# 07_EL_CON.net
KiCad netlist of a schematic drawn in Altium Designer
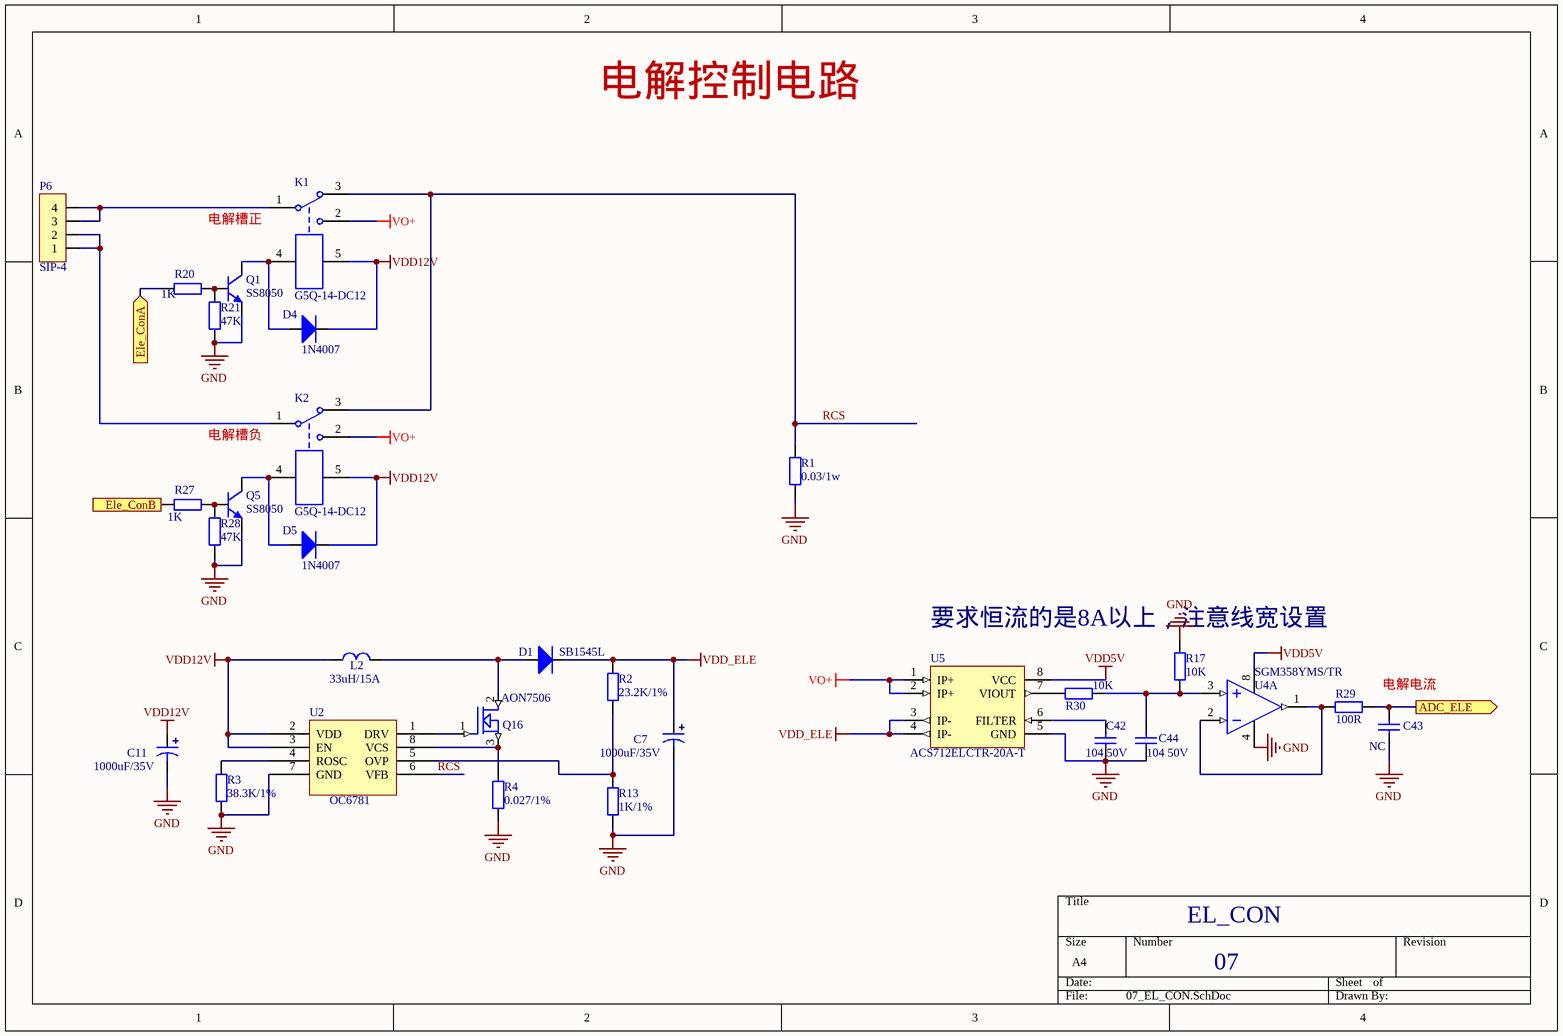
[diagram p0: 07_EL_CON.SchDoc]

(export (version "E")
  (design (tool "Eeschema 10.0.6"))
  (components
    (comp (ref "C7")
      (value "1000uF/35V")
      (footprint "10*16")
      (description "电解电容")
      (libsource (lib "XiaoyI") (part "CAP2"))
    )
    (comp (ref "C11")
      (value "1000uF/35V")
      (footprint "10*16")
      (description "电解电容")
      (libsource (lib "XiaoyI") (part "CAP2"))
    )
    (comp (ref "C42")
      (value "104 50V")
      (footprint "SMD-0603C")
      (description "贴片电容 10%")
      (libsource (lib "XiaoyI") (part "CAP4"))
    )
    (comp (ref "C43")
      (value "NC")
      (footprint "SMD-0603C")
      (description "贴片电容 10%")
      (libsource (lib "XiaoyI") (part "CAP4"))
    )
    (comp (ref "C44")
      (value "104 50V")
      (footprint "SMD-0603C")
      (description "贴片电容 10%")
      (libsource (lib "XiaoyI") (part "CAP4"))
    )
    (comp (ref "D1")
      (value "SB1545L")
      (footprint "TO227")
      (description "肖特基二极管")
      (libsource (lib "XiaoyI") (part "DIODE2"))
    )
    (comp (ref "D4")
      (value "1N4007")
      (footprint "DO-214-AC")
      (description "贴片二极管")
      (libsource (lib "XiaoyI") (part "DIODE2"))
    )
    (comp (ref "D5")
      (value "1N4007")
      (footprint "DO-214-AC")
      (description "贴片二极管")
      (libsource (lib "XiaoyI") (part "DIODE2"))
    )
    (comp (ref "K1")
      (value "G5Q-14-DC12")
      (footprint "G5Q-14")
      (description "5V 继电器")
      (libsource (lib "XiaoyI") (part "JDQ1"))
    )
    (comp (ref "K2")
      (value "G5Q-14-DC12")
      (footprint "G5Q-14")
      (description "5V 继电器")
      (libsource (lib "XiaoyI") (part "JDQ1"))
    )
    (comp (ref "L2")
      (value "33uH/15A")
      (footprint "INDUCTOR_34*18")
      (description "10uH 1A")
      (libsource (lib "XiaoyI") (part "Inductor1"))
    )
    (comp (ref "P6")
      (value "SIP-4")
      (footprint "VH-AW-3.96*4P")
      (description "3.96 4P 直插")
      (libsource (lib "XiaoyI") (part "SIP-4"))
    )
    (comp (ref "Q1")
      (value "SS8050")
      (footprint "SOT-23")
      (description "三极管")
      (libsource (lib "XiaoyI") (part "NPN-1"))
    )
    (comp (ref "Q5")
      (value "SS8050")
      (footprint "SOT-23")
      (description "三极管")
      (libsource (lib "XiaoyI") (part "NPN-1"))
    )
    (comp (ref "Q16")
      (value "AON7506")
      (footprint "DFN3*3-8")
      (description "MOSFET N")
      (libsource (lib "XiaoyI") (part "MOSFET N"))
    )
    (comp (ref "R1")
      (value "0.03/1w")
      (footprint "2512R")
      (description "贴片电阻 5%")
      (libsource (lib "") (part "RES2_1"))
    )
    (comp (ref "R2")
      (value "23.2K/1%")
      (footprint "SMD-0603")
      (description "贴片电阻 5%")
      (libsource (lib "") (part "RES2_1"))
    )
    (comp (ref "R3")
      (value "38.3K/1%")
      (footprint "SMD-0603")
      (description "贴片电阻 5%")
      (libsource (lib "") (part "RES2_1"))
    )
    (comp (ref "R4")
      (value "0.027/1%")
      (footprint "2512r")
      (description "贴片电阻 5%")
      (libsource (lib "") (part "RES2_1"))
    )
    (comp (ref "R13")
      (value "1K/1%")
      (footprint "SMD-0603")
      (description "贴片电阻 5%")
      (libsource (lib "") (part "RES2_1"))
    )
    (comp (ref "R17")
      (value "10K")
      (footprint "SMD-0603")
      (description "贴片电阻 1%")
      (libsource (lib "") (part "RES0_1"))
    )
    (comp (ref "R20")
      (value "1K")
      (footprint "SMD-0603")
      (description "贴片电阻 5%")
      (libsource (lib "XiaoyI") (part "RES2"))
    )
    (comp (ref "R21")
      (value "47K")
      (footprint "SMD-0603")
      (description "贴片电阻 5%")
      (libsource (lib "") (part "RES2_2"))
    )
    (comp (ref "R27")
      (value "1K")
      (footprint "SMD-0603")
      (description "贴片电阻 5%")
      (libsource (lib "XiaoyI") (part "RES2"))
    )
    (comp (ref "R28")
      (value "47K")
      (footprint "SMD-0603")
      (description "贴片电阻 5%")
      (libsource (lib "") (part "RES2_2"))
    )
    (comp (ref "R29")
      (value "100R")
      (footprint "SMD-0603")
      (description "贴片电阻 5%")
      (libsource (lib "ABB") (part "RES0"))
    )
    (comp (ref "R30")
      (value "10K")
      (footprint "SMD-0603")
      (description "贴片电阻 1%")
      (libsource (lib "ABB") (part "RES0"))
    )
    (comp (ref "U2")
      (value "OC6781")
      (footprint "SOP127P600X265_HS-9N")
      (libsource (lib "stm32") (part "OC6781"))
    )
    (comp (ref "U4")
      (value "SGM358YMS/TR")
      (footprint "MSOP-8")
      (description "运算放大器")
      (libsource (lib "XiaoyI") (part "LM358"))
    )
    (comp (ref "U5")
      (value "ACS712ELCTR-20A-T")
      (footprint "SO-8")
      (description "HALL 20A 电流传感器")
      (libsource (lib "XiaoyI") (part "ACS712"))
    )
  )
  (nets
    (net (code "1") (name "/ADC_ELE") (class "Default")
      (node (ref "C43") (pin "2") (pinfunction "2_2") (pintype "passive"))
      (node (ref "R29") (pin "1") (pinfunction "1_1") (pintype "passive"))
    )
    (net (code "2") (name "/Ele_ConA") (class "Default")
      (node (ref "R20") (pin "1") (pinfunction "1_1") (pintype "passive"))
    )
    (net (code "3") (name "/Ele_ConB") (class "Default")
      (node (ref "R27") (pin "1") (pinfunction "1_1") (pintype "passive"))
    )
    (net (code "4") (name "/RCS") (class "Default")
      (node (ref "K1") (pin "3") (pinfunction "3_3") (pintype "passive"))
      (node (ref "K2") (pin "3") (pinfunction "3_3") (pintype "passive"))
      (node (ref "R1") (pin "1") (pinfunction "1_1") (pintype "passive"))
      (node (ref "U2") (pin "6") (pinfunction "VFB_6") (pintype "passive"))
    )
    (net (code "5") (name "GND") (class "Default")
      (node (ref "C11") (pin "2") (pinfunction "2_2") (pintype "passive"))
      (node (ref "C42") (pin "2") (pinfunction "2_2") (pintype "passive"))
      (node (ref "C43") (pin "1") (pinfunction "1_1") (pintype "passive"))
      (node (ref "C44") (pin "2") (pinfunction "2_2") (pintype "passive"))
      (node (ref "C7") (pin "2") (pinfunction "2_2") (pintype "passive"))
      (node (ref "Q1") (pin "2") (pinfunction "E_2") (pintype "passive"))
      (node (ref "Q5") (pin "2") (pinfunction "E_2") (pintype "passive"))
      (node (ref "R1") (pin "2") (pinfunction "2_2") (pintype "passive"))
      (node (ref "R13") (pin "2") (pinfunction "2_2") (pintype "passive"))
      (node (ref "R17") (pin "1") (pinfunction "1_1") (pintype "passive"))
      (node (ref "R21") (pin "1") (pinfunction "1_1") (pintype "passive"))
      (node (ref "R28") (pin "1") (pinfunction "1_1") (pintype "passive"))
      (node (ref "R3") (pin "2") (pinfunction "2_2") (pintype "passive"))
      (node (ref "R4") (pin "2") (pinfunction "2_2") (pintype "passive"))
      (node (ref "U2") (pin "7") (pinfunction "GND_7") (pintype "passive"))
      (node (ref "U4") (pin "4") (pinfunction "V-_4") (pintype "power_in"))
      (node (ref "U5") (pin "5") (pinfunction "GND_5") (pintype "power_in"))
    )
    (net (code "6") (name "Net-(D1-A)") (class "Default")
      (node (ref "D1") (pin "1") (pinfunction "A_1") (pintype "passive"))
      (node (ref "L2") (pin "2") (pinfunction "2_2") (pintype "passive"))
      (node (ref "Q16") (pin "2") (pinfunction "D_2") (pintype "input"))
    )
    (net (code "7") (name "Net-(D4-A)") (class "Default")
      (node (ref "D4") (pin "1") (pinfunction "A_1") (pintype "passive"))
      (node (ref "K1") (pin "4") (pinfunction "4_4") (pintype "passive"))
      (node (ref "Q1") (pin "3") (pinfunction "C_3") (pintype "passive"))
    )
    (net (code "8") (name "Net-(D5-A)") (class "Default")
      (node (ref "D5") (pin "1") (pinfunction "A_1") (pintype "passive"))
      (node (ref "K2") (pin "4") (pinfunction "4_4") (pintype "passive"))
      (node (ref "Q5") (pin "3") (pinfunction "C_3") (pintype "passive"))
    )
    (net (code "9") (name "Net-(K1-Pad1)") (class "Default")
      (node (ref "K1") (pin "1") (pinfunction "1_1") (pintype "passive"))
      (node (ref "P6") (pin "3") (pinfunction "3_3") (pintype "passive"))
      (node (ref "P6") (pin "4") (pinfunction "4_4") (pintype "passive"))
    )
    (net (code "10") (name "Net-(K2-Pad1)") (class "Default")
      (node (ref "K2") (pin "1") (pinfunction "1_1") (pintype "passive"))
      (node (ref "P6") (pin "1") (pinfunction "1_1") (pintype "passive"))
      (node (ref "P6") (pin "2") (pinfunction "2_2") (pintype "passive"))
    )
    (net (code "11") (name "Net-(Q1-B)") (class "Default")
      (node (ref "Q1") (pin "1") (pinfunction "B_1") (pintype "passive"))
      (node (ref "R20") (pin "2") (pinfunction "2_2") (pintype "passive"))
      (node (ref "R21") (pin "2") (pinfunction "2_2") (pintype "passive"))
    )
    (net (code "12") (name "Net-(Q5-B)") (class "Default")
      (node (ref "Q5") (pin "1") (pinfunction "B_1") (pintype "passive"))
      (node (ref "R27") (pin "2") (pinfunction "2_2") (pintype "passive"))
      (node (ref "R28") (pin "2") (pinfunction "2_2") (pintype "passive"))
    )
    (net (code "13") (name "Net-(Q16-G)") (class "Default")
      (node (ref "Q16") (pin "1") (pinfunction "G_1") (pintype "input"))
      (node (ref "U2") (pin "1") (pinfunction "DRV_1") (pintype "passive"))
    )
    (net (code "14") (name "Net-(Q16-S)") (class "Default")
      (node (ref "Q16") (pin "3") (pinfunction "S_3") (pintype "output"))
      (node (ref "R4") (pin "1") (pinfunction "1_1") (pintype "passive"))
      (node (ref "U2") (pin "8") (pinfunction "VCS_8") (pintype "passive"))
    )
    (net (code "15") (name "Net-(U2-OVP)") (class "Default")
      (node (ref "R13") (pin "1") (pinfunction "1_1") (pintype "passive"))
      (node (ref "R2") (pin "2") (pinfunction "2_2") (pintype "passive"))
      (node (ref "U2") (pin "5") (pinfunction "OVP_5") (pintype "passive"))
    )
    (net (code "16") (name "Net-(U2-ROSC)") (class "Default")
      (node (ref "R3") (pin "1") (pinfunction "1_1") (pintype "passive"))
      (node (ref "U2") (pin "4") (pinfunction "ROSC_4") (pintype "passive"))
    )
    (net (code "17") (name "Net-(U4A-IN1+)") (class "Default")
      (node (ref "C44") (pin "1") (pinfunction "1_1") (pintype "passive"))
      (node (ref "R17") (pin "2") (pinfunction "2_2") (pintype "passive"))
      (node (ref "R30") (pin "1") (pinfunction "1_1") (pintype "passive"))
      (node (ref "U4") (pin "3") (pinfunction "IN1+_3") (pintype "input"))
    )
    (net (code "18") (name "Net-(U4A-IN1-)") (class "Default")
      (node (ref "R29") (pin "2") (pinfunction "2_2") (pintype "passive"))
      (node (ref "U4") (pin "1") (pinfunction "OUT1_1") (pintype "output"))
      (node (ref "U4") (pin "2") (pinfunction "IN1-_2") (pintype "input"))
    )
    (net (code "19") (name "Net-(U5-FILTER)") (class "Default")
      (node (ref "C42") (pin "1") (pinfunction "1_1") (pintype "passive"))
      (node (ref "U5") (pin "6") (pinfunction "FILTER_6") (pintype "input"))
    )
    (net (code "20") (name "Net-(U5-VIOUT)") (class "Default")
      (node (ref "R30") (pin "2") (pinfunction "2_2") (pintype "passive"))
      (node (ref "U5") (pin "7") (pinfunction "VIOUT_7") (pintype "output"))
    )
    (net (code "21") (name "VDD5V") (class "Default")
      (node (ref "U4") (pin "8") (pinfunction "V+_8") (pintype "power_in"))
      (node (ref "U5") (pin "8") (pinfunction "VCC_8") (pintype "power_in"))
    )
    (net (code "22") (name "VDD12V") (class "Default")
      (node (ref "C11") (pin "1") (pinfunction "1_1") (pintype "passive"))
      (node (ref "D4") (pin "2") (pinfunction "K_2") (pintype "passive"))
      (node (ref "D5") (pin "2") (pinfunction "K_2") (pintype "passive"))
      (node (ref "K1") (pin "5") (pinfunction "5_5") (pintype "passive"))
      (node (ref "K2") (pin "5") (pinfunction "5_5") (pintype "passive"))
      (node (ref "L2") (pin "1") (pinfunction "1_1") (pintype "passive"))
      (node (ref "U2") (pin "2") (pinfunction "VDD_2") (pintype "passive"))
      (node (ref "U2") (pin "3") (pinfunction "EN_3") (pintype "passive"))
    )
    (net (code "23") (name "VDD_ELE") (class "Default")
      (node (ref "C7") (pin "1") (pinfunction "1_1") (pintype "passive"))
      (node (ref "D1") (pin "2") (pinfunction "K_2") (pintype "passive"))
      (node (ref "R2") (pin "1") (pinfunction "1_1") (pintype "passive"))
      (node (ref "U5") (pin "3") (pinfunction "IP-_3") (pintype "output"))
      (node (ref "U5") (pin "4") (pinfunction "IP-_4") (pintype "output"))
    )
    (net (code "24") (name "VO+") (class "Default")
      (node (ref "K1") (pin "2") (pinfunction "2_2") (pintype "passive"))
      (node (ref "K2") (pin "2") (pinfunction "2_2") (pintype "passive"))
      (node (ref "U5") (pin "1") (pinfunction "IP+_1") (pintype "input"))
      (node (ref "U5") (pin "2") (pinfunction "IP+_2") (pintype "input"))
    )
  )
)
